# BUZZER.net
KiCad netlist of a schematic drawn in Altium Designer
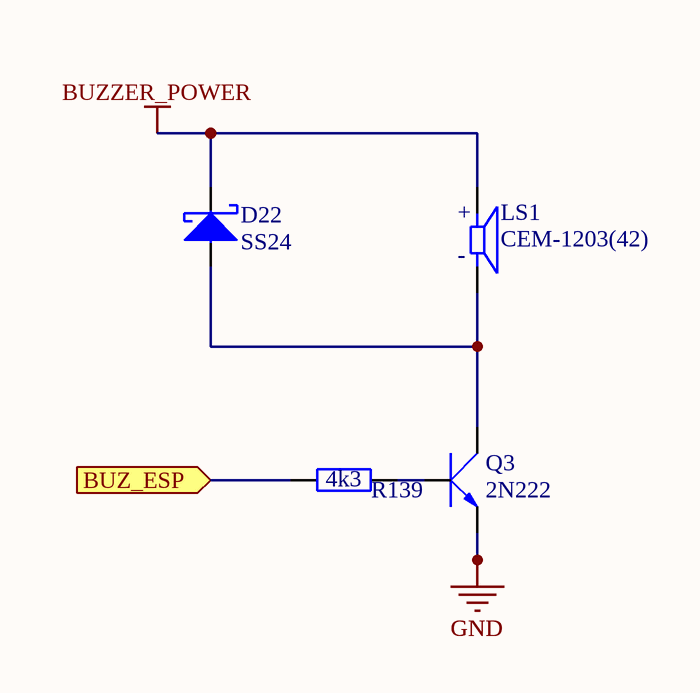
[diagram p0: BUZZER.SchDoc]

(export (version "E")
  (design (tool "Eeschema 10.0.6"))
  (components
    (comp (ref "D22")
      (value "SS24")
      (footprint "DIO-SMD-106")
      (description "Diode Schottky")
      (fields (field (name "PART NUMBER") "LED 3 ly Single Colour"))
      (libsource (lib "KhanhBK_Library_4") (part "Diode Schottky"))
    )
    (comp (ref "LS1")
      (value "CEM-1203(42)")
      (footprint "CUI_CEM-1203(42)")
      (description "12 mm, 3.5 V, 85 dB, Through Hole, Magnetic Audio Transducer Buzzer")
      (fields (field (name "MF") "CUI Devices"))
      (libsource (lib "BUZZER_CEM_1203_42") (part "CEM-1203(42)"))
    )
    (comp (ref "Q3")
      (value "2N222")
      (footprint "SOT23-231")
      (description "NPN 600mW, ECB")
      (libsource (lib "KhanhBK_Library_4") (part "2N222"))
    )
    (comp (ref "R139") (value "4k3") (footprint "0603_Res") (libsource (lib "CMN") (part "Resistor")))
  )
  (nets
    (net (code "1") (name "/BUZ_ESP") (class "Default")
      (node (ref "R139") (pin "1") (pinfunction "1_1") (pintype "passive"))
    )
    (net (code "2") (name "BUZZER_POWER") (class "Default")
      (node (ref "D22") (pin "2") (pinfunction "2_2") (pintype "passive"))
      (node (ref "LS1") (pin "P") (pinfunction "P_P") (pintype "passive"))
    )
    (net (code "3") (name "GND") (class "Default")
      (node (ref "Q3") (pin "1") (pinfunction "E_1") (pintype "passive"))
    )
    (net (code "4") (name "Net-(Q3-B)") (class "Default")
      (node (ref "Q3") (pin "2") (pinfunction "B_2") (pintype "passive"))
      (node (ref "R139") (pin "2") (pinfunction "2_2") (pintype "passive"))
    )
    (net (code "5") (name "Net-(Q3-C)") (class "Default")
      (node (ref "D22") (pin "1") (pinfunction "1_1") (pintype "passive"))
      (node (ref "LS1") (pin "N") (pinfunction "N_N") (pintype "passive"))
      (node (ref "Q3") (pin "3") (pinfunction "C_3") (pintype "passive"))
    )
  )
)
